# LT3652-MPPT.net
KiCad netlist of a schematic drawn in EAGLE
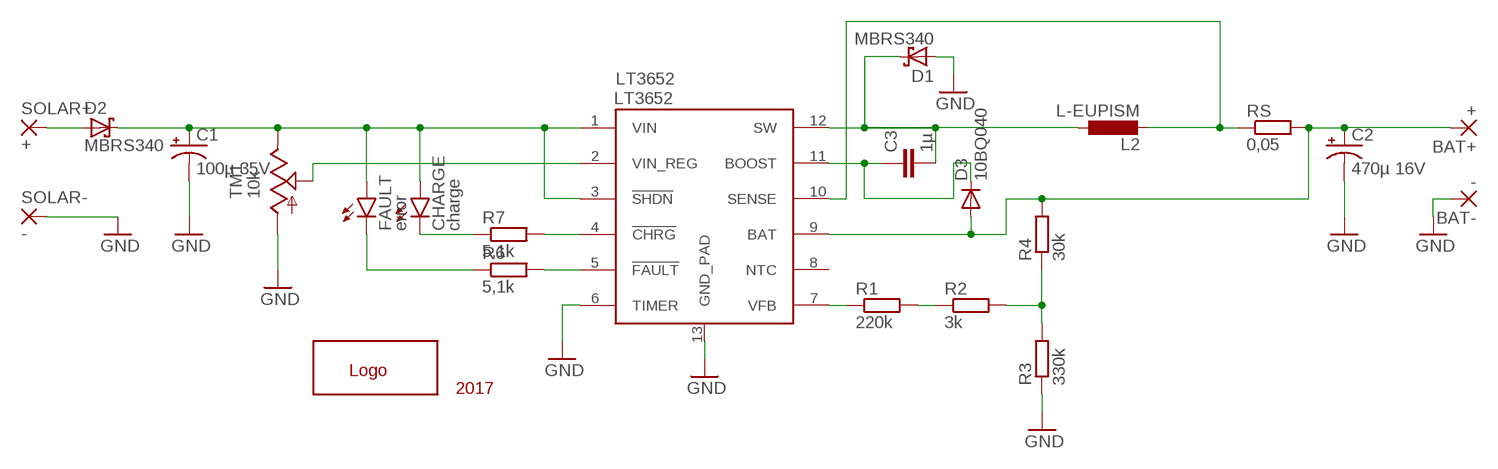
[diagram p0: schematic, sheet 1]

(export (version "E")
  (design (tool "Eeschema 10.0.6"))
  (components
    (comp (ref "BAT+")
      (value "+")
      (footprint "eagle-import:3,81_1,4")
      (libsource (lib "eagle-import") (part "3,81/1,4"))
    )
    (comp (ref "BAT-")
      (value "-")
      (footprint "eagle-import:3,81_1,4")
      (libsource (lib "eagle-import") (part "3,81/1,4"))
    )
    (comp (ref "C1")
      (value "100µ 35V")
      (footprint "eagle-import:PANASONIC_C")
      (libsource (lib "eagle-import") (part "CAP_POLC"))
    )
    (comp (ref "C2")
      (value "470µ 16V")
      (footprint "eagle-import:PANASONIC_C")
      (libsource (lib "eagle-import") (part "CAP_POLC"))
    )
    (comp (ref "C3")
      (value "1µ")
      (footprint "eagle-import:C0805")
      (libsource (lib "eagle-import") (part "C-EUC0805"))
    )
    (comp (ref "CHARGE")
      (value "charge")
      (footprint "eagle-import:LED-1206")
      (libsource (lib "eagle-import") (part "LED-BLUE1206"))
    )
    (comp (ref "D1")
      (value "MBRS340")
      (footprint "eagle-import:SMC")
      (libsource (lib "eagle-import") (part "SCHOTTKY-DIODESMC"))
    )
    (comp (ref "D2")
      (value "MBRS340")
      (footprint "eagle-import:SMC")
      (libsource (lib "eagle-import") (part "SCHOTTKY-DIODESMC"))
    )
    (comp (ref "D3")
      (value "10BQ040")
      (footprint "eagle-import:SMA-DIODE")
      (libsource (lib "eagle-import") (part "DIODESMA"))
    )
    (comp (ref "FAULT")
      (value "error")
      (footprint "eagle-import:LED-1206")
      (libsource (lib "eagle-import") (part "LED-RED1206"))
    )
    (comp (ref "L2")
      (value "L-EUPISM")
      (footprint "eagle-import:PISM")
      (libsource (lib "eagle-import") (part "L-EUPISM"))
    )
    (comp (ref "LT3652")
      (value "LT3652")
      (footprint "eagle-import:MSOP-12_GND")
      (libsource (lib "eagle-import") (part "LT3652"))
    )
    (comp (ref "R1")
      (value "220k")
      (footprint "eagle-import:R0805")
      (libsource (lib "eagle-import") (part "R-EU_R0805"))
    )
    (comp (ref "R2")
      (value "3k")
      (footprint "eagle-import:R0805")
      (libsource (lib "eagle-import") (part "R-EU_R0805"))
    )
    (comp (ref "R3")
      (value "330k")
      (footprint "eagle-import:R0805")
      (libsource (lib "eagle-import") (part "R-EU_R0805"))
    )
    (comp (ref "R4")
      (value "30k")
      (footprint "eagle-import:R0805")
      (libsource (lib "eagle-import") (part "R-EU_R0805"))
    )
    (comp (ref "R6")
      (value "5,1k")
      (footprint "eagle-import:R0805")
      (libsource (lib "eagle-import") (part "R-EU_R0805"))
    )
    (comp (ref "R7")
      (value "5,1k")
      (footprint "eagle-import:R0805")
      (libsource (lib "eagle-import") (part "R-EU_R0805"))
    )
    (comp (ref "RS")
      (value "0,05")
      (footprint "eagle-import:R1206")
      (libsource (lib "eagle-import") (part "R-EU_R1206"))
    )
    (comp (ref "SOLAR+")
      (value "+")
      (footprint "eagle-import:3,81_1,4")
      (libsource (lib "eagle-import") (part "3,81/1,4"))
    )
    (comp (ref "SOLAR-")
      (value "-")
      (footprint "eagle-import:3,81_1,4")
      (libsource (lib "eagle-import") (part "3,81/1,4"))
    )
    (comp (ref "TM1")
      (value "10k")
      (footprint "eagle-import:5MMP")
      (libsource (lib "eagle-import") (part "TRIM5MMP"))
    )
    (comp (ref "U$1")
      (value "2017")
      (footprint "eagle-import:LOGO")
      (libsource (lib "eagle-import") (part "LOGO1"))
    )
  )
  (nets
    (net (code "1") (name "GND") (class "Default")
      (node (ref "BAT-") (pin "1") (pinfunction "P_1") (pintype "passive"))
      (node (ref "C1") (pin "-") (pinfunction "-_-") (pintype "passive"))
      (node (ref "C2") (pin "-") (pinfunction "-_-") (pintype "passive"))
      (node (ref "D1") (pin "A") (pinfunction "A_A") (pintype "passive"))
      (node (ref "LT3652") (pin "13") (pinfunction "GND_PAD_13") (pintype "bidirectional"))
      (node (ref "LT3652") (pin "6") (pinfunction "TIMER_6") (pintype "bidirectional"))
      (node (ref "R3") (pin "1") (pinfunction "1_1") (pintype "passive"))
      (node (ref "SOLAR-") (pin "1") (pinfunction "P_1") (pintype "passive"))
      (node (ref "TM1") (pin "A") (pinfunction "A_A") (pintype "passive"))
    )
    (net (code "2") (name "Net-(BAT+-P)") (class "Default")
      (node (ref "BAT+") (pin "1") (pinfunction "P_1") (pintype "passive"))
      (node (ref "C2") (pin "+") (pinfunction "+_+") (pintype "passive"))
      (node (ref "D3") (pin "A") (pinfunction "A_A") (pintype "passive"))
      (node (ref "LT3652") (pin "9") (pinfunction "BAT_9") (pintype "bidirectional"))
      (node (ref "R4") (pin "2") (pinfunction "2_2") (pintype "passive"))
      (node (ref "RS") (pin "2") (pinfunction "2_2") (pintype "passive"))
    )
    (net (code "3") (name "Net-(CHARGE-PadC)") (class "Default")
      (node (ref "CHARGE") (pin "C") (pinfunction "C_C") (pintype "passive"))
      (node (ref "R7") (pin "1") (pinfunction "1_1") (pintype "passive"))
    )
    (net (code "4") (name "Net-(FAULT-PadC)") (class "Default")
      (node (ref "FAULT") (pin "C") (pinfunction "C_C") (pintype "passive"))
      (node (ref "R6") (pin "1") (pinfunction "1_1") (pintype "passive"))
    )
    (net (code "5") (name "Net-(LT3652-BOOST)") (class "Default")
      (node (ref "C3") (pin "1") (pinfunction "1_1") (pintype "passive"))
      (node (ref "D3") (pin "C") (pinfunction "C_C") (pintype "passive"))
      (node (ref "LT3652") (pin "11") (pinfunction "BOOST_11") (pintype "bidirectional"))
    )
    (net (code "6") (name "Net-(LT3652-SENSE)") (class "Default")
      (node (ref "L2") (pin "2") (pinfunction "2_2") (pintype "passive"))
      (node (ref "LT3652") (pin "10") (pinfunction "SENSE_10") (pintype "bidirectional"))
      (node (ref "RS") (pin "1") (pinfunction "1_1") (pintype "passive"))
    )
    (net (code "7") (name "Net-(LT3652-SW)") (class "Default")
      (node (ref "C3") (pin "2") (pinfunction "2_2") (pintype "passive"))
      (node (ref "D1") (pin "C") (pinfunction "C_C") (pintype "passive"))
      (node (ref "L2") (pin "1") (pinfunction "1_1") (pintype "passive"))
      (node (ref "LT3652") (pin "12") (pinfunction "SW_12") (pintype "bidirectional"))
    )
    (net (code "8") (name "Net-(LT3652-VFB)") (class "Default")
      (node (ref "LT3652") (pin "7") (pinfunction "VFB_7") (pintype "bidirectional"))
      (node (ref "R1") (pin "1") (pinfunction "1_1") (pintype "passive"))
    )
    (net (code "9") (name "Net-(LT3652-VIN)") (class "Default")
      (node (ref "C1") (pin "+") (pinfunction "+_+") (pintype "passive"))
      (node (ref "CHARGE") (pin "A") (pinfunction "A_A") (pintype "passive"))
      (node (ref "D2") (pin "C") (pinfunction "C_C") (pintype "passive"))
      (node (ref "FAULT") (pin "A") (pinfunction "A_A") (pintype "passive"))
      (node (ref "LT3652") (pin "1") (pinfunction "VIN_1") (pintype "bidirectional"))
      (node (ref "LT3652") (pin "3") (pinfunction "~{SHDN}_3") (pintype "bidirectional"))
      (node (ref "TM1") (pin "E") (pinfunction "E_E") (pintype "passive"))
    )
    (net (code "10") (name "Net-(LT3652-VIN_REG)") (class "Default")
      (node (ref "LT3652") (pin "2") (pinfunction "VIN_REG_2") (pintype "bidirectional"))
      (node (ref "TM1") (pin "S") (pinfunction "S_S") (pintype "passive"))
    )
    (net (code "11") (name "Net-(LT3652-~{CHRG})") (class "Default")
      (node (ref "LT3652") (pin "4") (pinfunction "~{CHRG}_4") (pintype "bidirectional"))
      (node (ref "R7") (pin "2") (pinfunction "2_2") (pintype "passive"))
    )
    (net (code "12") (name "Net-(LT3652-~{FAULT})") (class "Default")
      (node (ref "LT3652") (pin "5") (pinfunction "~{FAULT}_5") (pintype "bidirectional"))
      (node (ref "R6") (pin "2") (pinfunction "2_2") (pintype "passive"))
    )
    (net (code "13") (name "Net-(R1-Pad2)") (class "Default")
      (node (ref "R1") (pin "2") (pinfunction "2_2") (pintype "passive"))
      (node (ref "R2") (pin "1") (pinfunction "1_1") (pintype "passive"))
    )
    (net (code "14") (name "Net-(R2-Pad2)") (class "Default")
      (node (ref "R2") (pin "2") (pinfunction "2_2") (pintype "passive"))
      (node (ref "R3") (pin "2") (pinfunction "2_2") (pintype "passive"))
      (node (ref "R4") (pin "1") (pinfunction "1_1") (pintype "passive"))
    )
    (net (code "15") (name "Net-(SOLAR+-P)") (class "Default")
      (node (ref "D2") (pin "A") (pinfunction "A_A") (pintype "passive"))
      (node (ref "SOLAR+") (pin "1") (pinfunction "P_1") (pintype "passive"))
    )
    (net (code "16") (name "unconnected-(LT3652-NTC-Pad8)") (class "Default")
      (node (ref "LT3652") (pin "8") (pinfunction "NTC_8") (pintype "bidirectional"))
    )
  )
)
